# lcd_duffle_smd_mk_1.net
KiCad netlist of a schematic drawn in EAGLE
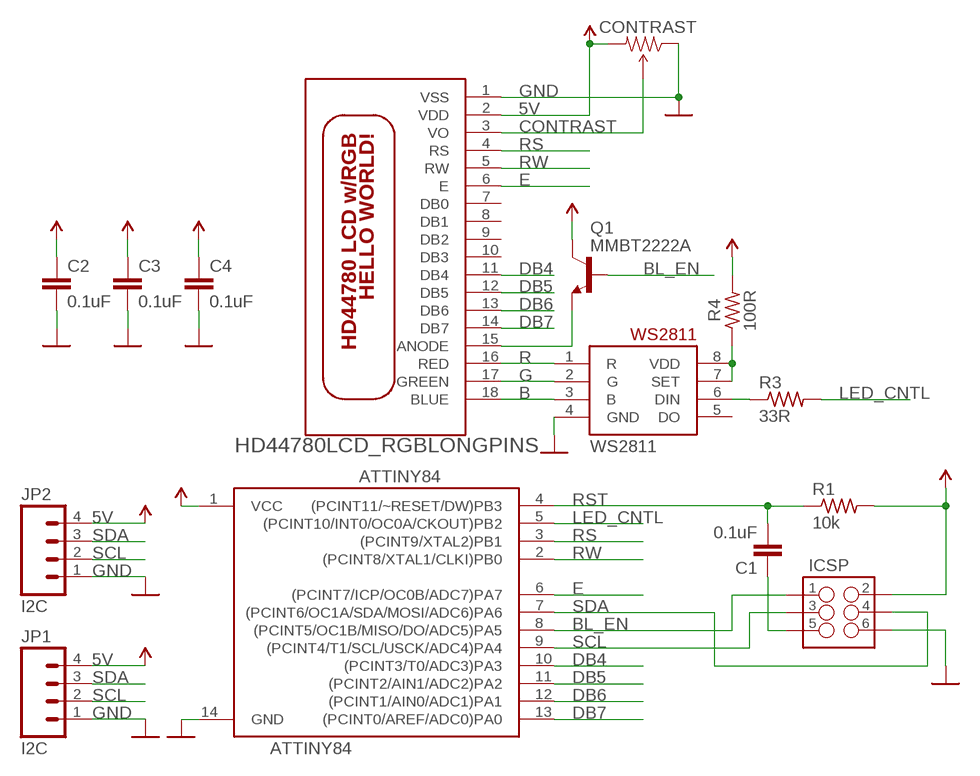
[diagram p0: schematic, sheet 1]

(export (version "E")
  (design (tool "Eeschema 10.0.6"))
  (components
    (comp (ref "ATTINY84")
      (value "ATTINY84")
      (footprint "eagle-import:SO14")
      (libsource (lib "eagle-import") (part "ATTINY84"))
    )
    (comp (ref "C1")
      (value "0.1uF")
      (footprint "eagle-import:C0603")
      (libsource (lib "eagle-import") (part "CAPACITOR-CERAMICC0603"))
    )
    (comp (ref "C2")
      (value "0.1uF")
      (footprint "eagle-import:C0603")
      (libsource (lib "eagle-import") (part "CAPACITOR-CERAMICC0603"))
    )
    (comp (ref "C3")
      (value "0.1uF")
      (footprint "eagle-import:C0603")
      (libsource (lib "eagle-import") (part "CAPACITOR-CERAMICC0603"))
    )
    (comp (ref "C4")
      (value "0.1uF")
      (footprint "eagle-import:C0603")
      (libsource (lib "eagle-import") (part "CAPACITOR-CERAMICC0603"))
    )
    (comp (ref "CONTRAST")
      (value "TRIMPOT")
      (footprint "eagle-import:TRIMPOT-5MM-V2")
      (libsource (lib "eagle-import") (part "TRIMPOT"))
    )
    (comp (ref "ICSP")
      (value "M03X2POGO_PINS")
      (footprint "eagle-import:2X3_POGO")
      (libsource (lib "eagle-import") (part "M03X2POGO_PINS"))
    )
    (comp (ref "JP1")
      (value "I2C")
      (footprint "eagle-import:1X04-SMD_LONG")
      (libsource (lib "eagle-import") (part "M04SMD_LONG"))
    )
    (comp (ref "JP2")
      (value "I2C")
      (footprint "eagle-import:1X04-SMD_LONG")
      (libsource (lib "eagle-import") (part "M04SMD_LONG"))
    )
    (comp (ref "Q1")
      (value "MMBT2222A")
      (footprint "eagle-import:SOT23-3")
      (libsource (lib "eagle-import") (part "TRANSISTOR_NPNMMBT2222A"))
    )
    (comp (ref "R1")
      (value "10k")
      (footprint "eagle-import:R0603")
      (libsource (lib "eagle-import") (part "RESISTORR0603"))
    )
    (comp (ref "R3")
      (value "33R")
      (footprint "eagle-import:R0603")
      (libsource (lib "eagle-import") (part "RESISTORR0603"))
    )
    (comp (ref "R4")
      (value "100R")
      (footprint "eagle-import:R0603")
      (libsource (lib "eagle-import") (part "RESISTORR0603"))
    )
    (comp (ref "U$1")
      (value "HD44780LCD_RGBLONGPINS")
      (footprint "eagle-import:LCD1602-RGB")
      (libsource (lib "eagle-import") (part "HD44780LCD_RGBLONGPINS"))
    )
    (comp (ref "WS2811")
      (value "WS2811-SOP8")
      (footprint "eagle-import:SO08-SKINNYPADS")
      (libsource (lib "eagle-import") (part "WS2811-SOP8"))
    )
  )
  (nets
    (net (code "1") (name "/B") (class "Default")
      (node (ref "U$1") (pin "18") (pinfunction "BLUE_18") (pintype "input"))
      (node (ref "WS2811") (pin "3") (pinfunction "B_3") (pintype "open_collector"))
    )
    (net (code "2") (name "/BL_EN") (class "Default")
      (node (ref "ATTINY84") (pin "8") (pinfunction "(PCINT5/OC1B/MISO/DO/ADC5)PA5_8") (pintype "bidirectional"))
      (node (ref "ICSP") (pin "P$1") (pinfunction "1_P$1") (pintype "bidirectional"))
      (node (ref "Q1") (pin "1") (pinfunction "B_1") (pintype "passive"))
    )
    (net (code "3") (name "/CONTRAST") (class "Default")
      (node (ref "CONTRAST") (pin "B") (pinfunction "WIPER_B") (pintype "passive"))
      (node (ref "U$1") (pin "3") (pinfunction "VO_3") (pintype "input"))
    )
    (net (code "4") (name "/DB4") (class "Default")
      (node (ref "ATTINY84") (pin "10") (pinfunction "(PCINT3/T0/ADC3)PA3_10") (pintype "bidirectional"))
      (node (ref "U$1") (pin "11") (pinfunction "DB4_11") (pintype "bidirectional"))
    )
    (net (code "5") (name "/DB5") (class "Default")
      (node (ref "ATTINY84") (pin "11") (pinfunction "(PCINT2/AIN1/ADC2)PA2_11") (pintype "bidirectional"))
      (node (ref "U$1") (pin "12") (pinfunction "DB5_12") (pintype "bidirectional"))
    )
    (net (code "6") (name "/DB6") (class "Default")
      (node (ref "ATTINY84") (pin "12") (pinfunction "(PCINT1/AIN0/ADC1)PA1_12") (pintype "bidirectional"))
      (node (ref "U$1") (pin "13") (pinfunction "DB6_13") (pintype "bidirectional"))
    )
    (net (code "7") (name "/DB7") (class "Default")
      (node (ref "ATTINY84") (pin "13") (pinfunction "(PCINT0/AREF/ADC0)PA0_13") (pintype "bidirectional"))
      (node (ref "U$1") (pin "14") (pinfunction "DB7_14") (pintype "bidirectional"))
    )
    (net (code "8") (name "/E") (class "Default")
      (node (ref "ATTINY84") (pin "6") (pinfunction "(PCINT7/ICP/OC0B/ADC7)PA7_6") (pintype "bidirectional"))
      (node (ref "U$1") (pin "6") (pinfunction "E_6") (pintype "input"))
    )
    (net (code "9") (name "/G") (class "Default")
      (node (ref "U$1") (pin "17") (pinfunction "GREEN_17") (pintype "input"))
      (node (ref "WS2811") (pin "2") (pinfunction "G_2") (pintype "open_collector"))
    )
    (net (code "10") (name "/LED_CNTL") (class "Default")
      (node (ref "ATTINY84") (pin "5") (pinfunction "(PCINT10/INT0/OC0A/CKOUT)PB2_5") (pintype "bidirectional"))
      (node (ref "R3") (pin "2") (pinfunction "2_2") (pintype "passive"))
    )
    (net (code "11") (name "/R") (class "Default")
      (node (ref "U$1") (pin "16") (pinfunction "RED_16") (pintype "input"))
      (node (ref "WS2811") (pin "1") (pinfunction "R_1") (pintype "open_collector"))
    )
    (net (code "12") (name "/RS") (class "Default")
      (node (ref "ATTINY84") (pin "3") (pinfunction "(PCINT9/XTAL2)PB1_3") (pintype "bidirectional"))
      (node (ref "U$1") (pin "4") (pinfunction "RS_4") (pintype "input"))
    )
    (net (code "13") (name "/RST") (class "Default")
      (node (ref "ATTINY84") (pin "4") (pinfunction "(PCINT11/~{RESET/DW})PB3_4") (pintype "bidirectional"))
      (node (ref "C1") (pin "2") (pinfunction "2_2") (pintype "passive"))
      (node (ref "R1") (pin "1") (pinfunction "1_1") (pintype "passive"))
    )
    (net (code "14") (name "/RW") (class "Default")
      (node (ref "ATTINY84") (pin "2") (pinfunction "(PCINT8/XTAL1/CLKI)PB0_2") (pintype "bidirectional"))
      (node (ref "U$1") (pin "5") (pinfunction "RW_5") (pintype "input"))
    )
    (net (code "15") (name "/SCL") (class "Default")
      (node (ref "ATTINY84") (pin "9") (pinfunction "(PCINT4/T1/SCL/USCK/ADC4)PA4_9") (pintype "bidirectional"))
      (node (ref "ICSP") (pin "P$3") (pinfunction "3_P$3") (pintype "bidirectional"))
      (node (ref "JP1") (pin "2") (pinfunction "2_2") (pintype "passive"))
      (node (ref "JP2") (pin "2") (pinfunction "2_2") (pintype "passive"))
    )
    (net (code "16") (name "/SDA") (class "Default")
      (node (ref "ATTINY84") (pin "7") (pinfunction "(PCINT6/OC1A/SDA/MOSI/ADC6)PA6_7") (pintype "bidirectional"))
      (node (ref "ICSP") (pin "P$4") (pinfunction "4_P$4") (pintype "bidirectional"))
      (node (ref "JP1") (pin "3") (pinfunction "3_3") (pintype "passive"))
      (node (ref "JP2") (pin "3") (pinfunction "3_3") (pintype "passive"))
    )
    (net (code "17") (name "5V") (class "Default")
      (node (ref "ATTINY84") (pin "1") (pinfunction "VCC_1") (pintype "bidirectional"))
      (node (ref "C2") (pin "2") (pinfunction "2_2") (pintype "passive"))
      (node (ref "C3") (pin "2") (pinfunction "2_2") (pintype "passive"))
      (node (ref "C4") (pin "2") (pinfunction "2_2") (pintype "passive"))
      (node (ref "CONTRAST") (pin "C") (pinfunction "CW_C") (pintype "passive"))
      (node (ref "ICSP") (pin "P$2") (pinfunction "2_P$2") (pintype "bidirectional"))
      (node (ref "JP1") (pin "4") (pinfunction "4_4") (pintype "passive"))
      (node (ref "JP2") (pin "4") (pinfunction "4_4") (pintype "passive"))
      (node (ref "Q1") (pin "3") (pinfunction "C_3") (pintype "passive"))
      (node (ref "R1") (pin "2") (pinfunction "2_2") (pintype "passive"))
      (node (ref "R4") (pin "2") (pinfunction "2_2") (pintype "passive"))
      (node (ref "U$1") (pin "2") (pinfunction "VDD_2") (pintype "power_in"))
    )
    (net (code "18") (name "GND") (class "Default")
      (node (ref "ATTINY84") (pin "14") (pinfunction "GND_14") (pintype "bidirectional"))
      (node (ref "C2") (pin "1") (pinfunction "1_1") (pintype "passive"))
      (node (ref "C3") (pin "1") (pinfunction "1_1") (pintype "passive"))
      (node (ref "C4") (pin "1") (pinfunction "1_1") (pintype "passive"))
      (node (ref "CONTRAST") (pin "A") (pinfunction "CCW_A") (pintype "passive"))
      (node (ref "ICSP") (pin "P$6") (pinfunction "6_P$6") (pintype "bidirectional"))
      (node (ref "JP1") (pin "1") (pinfunction "1_1") (pintype "passive"))
      (node (ref "JP2") (pin "1") (pinfunction "1_1") (pintype "passive"))
      (node (ref "U$1") (pin "1") (pinfunction "VSS_1") (pintype "power_in"))
      (node (ref "WS2811") (pin "4") (pinfunction "GND_4") (pintype "power_in"))
    )
    (net (code "19") (name "Net-(ICSP-5)") (class "Default")
      (node (ref "C1") (pin "1") (pinfunction "1_1") (pintype "passive"))
      (node (ref "ICSP") (pin "P$5") (pinfunction "5_P$5") (pintype "bidirectional"))
    )
    (net (code "20") (name "Net-(Q1-E)") (class "Default")
      (node (ref "Q1") (pin "2") (pinfunction "E_2") (pintype "passive"))
      (node (ref "U$1") (pin "15") (pinfunction "ANODE_15") (pintype "input"))
    )
    (net (code "21") (name "Net-(WS2811-DIN)") (class "Default")
      (node (ref "R3") (pin "1") (pinfunction "1_1") (pintype "passive"))
      (node (ref "WS2811") (pin "6") (pinfunction "DIN_6") (pintype "input"))
    )
    (net (code "22") (name "Net-(WS2811-SET)") (class "Default")
      (node (ref "R4") (pin "1") (pinfunction "1_1") (pintype "passive"))
      (node (ref "WS2811") (pin "7") (pinfunction "SET_7") (pintype "input"))
      (node (ref "WS2811") (pin "8") (pinfunction "VDD_8") (pintype "power_in"))
    )
    (net (code "23") (name "unconnected-(U$1-DB0-Pad7)") (class "Default")
      (node (ref "U$1") (pin "7") (pinfunction "DB0_7") (pintype "bidirectional"))
    )
    (net (code "24") (name "unconnected-(U$1-DB1-Pad8)") (class "Default")
      (node (ref "U$1") (pin "8") (pinfunction "DB1_8") (pintype "bidirectional"))
    )
    (net (code "25") (name "unconnected-(U$1-DB2-Pad9)") (class "Default")
      (node (ref "U$1") (pin "9") (pinfunction "DB2_9") (pintype "bidirectional"))
    )
    (net (code "26") (name "unconnected-(U$1-DB3-Pad10)") (class "Default")
      (node (ref "U$1") (pin "10") (pinfunction "DB3_10") (pintype "bidirectional"))
    )
    (net (code "27") (name "unconnected-(WS2811-DO-Pad5)") (class "Default")
      (node (ref "WS2811") (pin "5") (pinfunction "DO_5") (pintype "output"))
    )
  )
)
